# LEDs_and_Buttons.net
KiCad netlist of a schematic drawn in Altium Designer
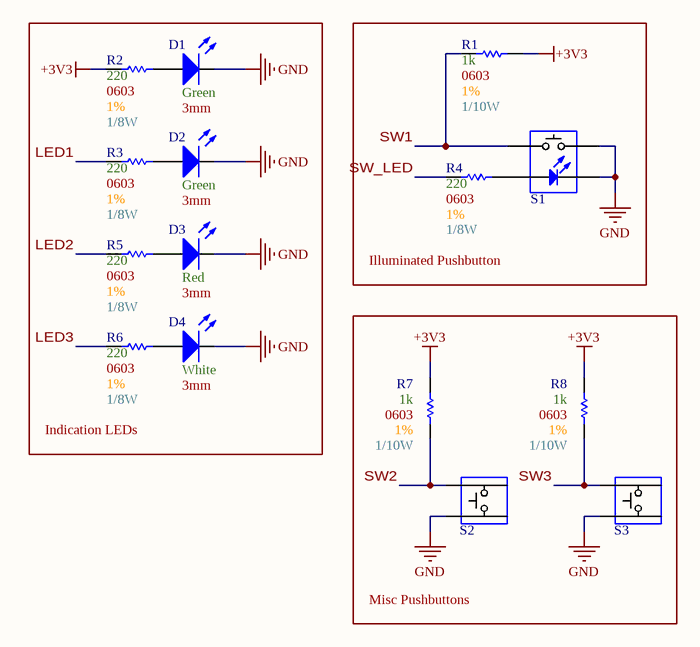
[diagram p0: LEDs and Buttons.SchDoc]

(export (version "E")
  (design (tool "Eeschema 10.0.6"))
  (components
    (comp (ref "D1")
      (value "[LED] Thru-Hole 3mm Green")
      (footprint "[LED] Thru-Hole 3mm")
      (description "151031VS06000")
      (fields (field (name "COLOR") "Green") (field (name "LENS DIAMETER") "3mm"))
      (libsource (lib "LEDs") (part "[LED] Thru-Hole 3mm Green"))
    )
    (comp (ref "D2")
      (value "[LED] Thru-Hole 3mm Green")
      (footprint "[LED] Thru-Hole 3mm")
      (description "151031VS06000")
      (fields (field (name "COLOR") "Green") (field (name "LENS DIAMETER") "3mm"))
      (libsource (lib "LEDs") (part "[LED] Thru-Hole 3mm Green"))
    )
    (comp (ref "D3")
      (value "[LED] Thru-Hole 3mm Red")
      (footprint "[LED] Thru-Hole 3mm")
      (description "151031SS06000")
      (fields (field (name "COLOR") "Red") (field (name "LENS DIAMETER") "3mm"))
      (libsource (lib "LEDs") (part "[LED] Thru-Hole 3mm Red"))
    )
    (comp (ref "D4")
      (value "[LED] Thru-Hole 3mm White")
      (footprint "[LED] Thru-Hole 3mm")
      (description "151031VS06000")
      (fields (field (name "COLOR") "White") (field (name "LENS DIAMETER") "3mm"))
      (libsource (lib "LEDs") (part "[LED] Thru-Hole 3mm White"))
    )
    (comp (ref "R1")
      (value "[1k] SMD 0603 1% 1/10W")
      (footprint "[Res] SMD 0603")
      (description "RMCF0603FT1K00")
      (fields
        (field (name "WATTAGE") "1/10W")
        (field (name "TOLERANCE") "1%")
        (field (name "RESISTANCE") "1k")
        (field (name "SIZE PACKAGE") "0603")
      )
      (libsource (lib "Resistors") (part "[1k] SMD 0603 1% 1/10W"))
    )
    (comp (ref "R2")
      (value "[220] SMD 0603 1% 1/10W")
      (footprint "[Res] SMD 0603")
      (description "CRGCQ0805F220R")
      (fields
        (field (name "WATTAGE") "1/8W")
        (field (name "TOLERANCE") "1%")
        (field (name "RESISTANCE") "220")
        (field (name "SIZE PACKAGE") "0603")
      )
      (libsource (lib "Resistors") (part "[220] SMD 0603 1% 1/10W"))
    )
    (comp (ref "R3")
      (value "[220] SMD 0603 1% 1/10W")
      (footprint "[Res] SMD 0603")
      (description "CRGCQ0805F220R")
      (fields
        (field (name "WATTAGE") "1/8W")
        (field (name "TOLERANCE") "1%")
        (field (name "RESISTANCE") "220")
        (field (name "SIZE PACKAGE") "0603")
      )
      (libsource (lib "Resistors") (part "[220] SMD 0603 1% 1/10W"))
    )
    (comp (ref "R4")
      (value "[220] SMD 0603 1% 1/10W")
      (footprint "[Res] SMD 0603")
      (description "CRGCQ0805F220R")
      (fields
        (field (name "WATTAGE") "1/8W")
        (field (name "TOLERANCE") "1%")
        (field (name "RESISTANCE") "220")
        (field (name "SIZE PACKAGE") "0603")
      )
      (libsource (lib "Resistors") (part "[220] SMD 0603 1% 1/10W"))
    )
    (comp (ref "R5")
      (value "[220] SMD 0603 1% 1/10W")
      (footprint "[Res] SMD 0603")
      (description "CRGCQ0805F220R")
      (fields
        (field (name "WATTAGE") "1/8W")
        (field (name "TOLERANCE") "1%")
        (field (name "RESISTANCE") "220")
        (field (name "SIZE PACKAGE") "0603")
      )
      (libsource (lib "Resistors") (part "[220] SMD 0603 1% 1/10W"))
    )
    (comp (ref "R6")
      (value "[220] SMD 0603 1% 1/10W")
      (footprint "[Res] SMD 0603")
      (description "CRGCQ0805F220R")
      (fields
        (field (name "WATTAGE") "1/8W")
        (field (name "TOLERANCE") "1%")
        (field (name "RESISTANCE") "220")
        (field (name "SIZE PACKAGE") "0603")
      )
      (libsource (lib "Resistors") (part "[220] SMD 0603 1% 1/10W"))
    )
    (comp (ref "R7")
      (value "[1k] SMD 0603 1% 1/10W")
      (footprint "[Res] SMD 0603")
      (description "RMCF0603FT1K00")
      (fields
        (field (name "WATTAGE") "1/10W")
        (field (name "TOLERANCE") "1%")
        (field (name "RESISTANCE") "1k")
        (field (name "SIZE PACKAGE") "0603")
      )
      (libsource (lib "Resistors") (part "[1k] SMD 0603 1% 1/10W"))
    )
    (comp (ref "R8")
      (value "[1k] SMD 0603 1% 1/10W")
      (footprint "[Res] SMD 0603")
      (description "RMCF0603FT1K00")
      (fields
        (field (name "WATTAGE") "1/10W")
        (field (name "TOLERANCE") "1%")
        (field (name "RESISTANCE") "1k")
        (field (name "SIZE PACKAGE") "0603")
      )
      (libsource (lib "Resistors") (part "[1k] SMD 0603 1% 1/10W"))
    )
    (comp (ref "S1")
      (value "[SPST] Illuminated Red Pushbutton")
      (footprint "[SPST] Illuminated Red Pushbutton")
      (description "B3W-9010-R1N")
      (libsource (lib "Switches") (part "[SPST] Illuminated Red Pushbutton"))
    )
    (comp (ref "S2")
      (value "Standard pushbutton")
      (footprint "[SPST] Pushbutton")
      (libsource (lib "Switches") (part "[SPST] Pushbutton"))
    )
    (comp (ref "S3")
      (value "Standard pushbutton")
      (footprint "[SPST] Pushbutton")
      (libsource (lib "Switches") (part "[SPST] Pushbutton"))
    )
  )
  (nets
    (net (code "1") (name "+3V3") (class "Default")
      (node (ref "R1") (pin "1") (pinfunction "1_1") (pintype "passive"))
      (node (ref "R2") (pin "1") (pinfunction "1_1") (pintype "passive"))
      (node (ref "R7") (pin "1") (pinfunction "1_1") (pintype "passive"))
      (node (ref "R8") (pin "1") (pinfunction "1_1") (pintype "passive"))
    )
    (net (code "2") (name "/LED1") (class "Default")
      (node (ref "R3") (pin "1") (pinfunction "1_1") (pintype "passive"))
    )
    (net (code "3") (name "/LED2") (class "Default")
      (node (ref "R5") (pin "1") (pinfunction "1_1") (pintype "passive"))
    )
    (net (code "4") (name "/LED3") (class "Default")
      (node (ref "R6") (pin "1") (pinfunction "1_1") (pintype "passive"))
    )
    (net (code "5") (name "/SW1") (class "Default")
      (node (ref "R1") (pin "2") (pinfunction "2_2") (pintype "passive"))
      (node (ref "S1") (pin "1") (pinfunction "NO_1_1") (pintype "passive"))
    )
    (net (code "6") (name "/SW2") (class "Default")
      (node (ref "R7") (pin "2") (pinfunction "2_2") (pintype "passive"))
      (node (ref "S2") (pin "1") (pintype "power_in"))
    )
    (net (code "7") (name "/SW3") (class "Default")
      (node (ref "R8") (pin "2") (pinfunction "2_2") (pintype "passive"))
      (node (ref "S3") (pin "1") (pintype "power_in"))
    )
    (net (code "8") (name "/SW_LED") (class "Default")
      (node (ref "R4") (pin "1") (pinfunction "1_1") (pintype "passive"))
    )
    (net (code "9") (name "GND") (class "Default")
      (node (ref "D1") (pin "2") (pinfunction "Cathode_2") (pintype "passive"))
      (node (ref "D2") (pin "2") (pinfunction "Cathode_2") (pintype "passive"))
      (node (ref "D3") (pin "2") (pinfunction "Cathode_2") (pintype "passive"))
      (node (ref "D4") (pin "2") (pinfunction "Cathode_2") (pintype "passive"))
      (node (ref "S1") (pin "2") (pinfunction "COM_1_2") (pintype "passive"))
      (node (ref "S1") (pin "6") (pinfunction "K_6") (pintype "passive"))
      (node (ref "S2") (pin "2") (pintype "power_in"))
      (node (ref "S3") (pin "2") (pintype "power_in"))
    )
    (net (code "10") (name "Net-(D1-Anode)") (class "Default")
      (node (ref "D1") (pin "1") (pinfunction "Anode_1") (pintype "passive"))
      (node (ref "R2") (pin "2") (pinfunction "2_2") (pintype "passive"))
    )
    (net (code "11") (name "Net-(D2-Anode)") (class "Default")
      (node (ref "D2") (pin "1") (pinfunction "Anode_1") (pintype "passive"))
      (node (ref "R3") (pin "2") (pinfunction "2_2") (pintype "passive"))
    )
    (net (code "12") (name "Net-(D3-Anode)") (class "Default")
      (node (ref "D3") (pin "1") (pinfunction "Anode_1") (pintype "passive"))
      (node (ref "R5") (pin "2") (pinfunction "2_2") (pintype "passive"))
    )
    (net (code "13") (name "Net-(D4-Anode)") (class "Default")
      (node (ref "D4") (pin "1") (pinfunction "Anode_1") (pintype "passive"))
      (node (ref "R6") (pin "2") (pinfunction "2_2") (pintype "passive"))
    )
    (net (code "14") (name "Net-(S1-A)") (class "Default")
      (node (ref "R4") (pin "2") (pinfunction "2_2") (pintype "passive"))
      (node (ref "S1") (pin "5") (pinfunction "A_5") (pintype "passive"))
    )
  )
)
